# Jlink_OB.net
KiCad netlist of a schematic drawn in Altium Designer
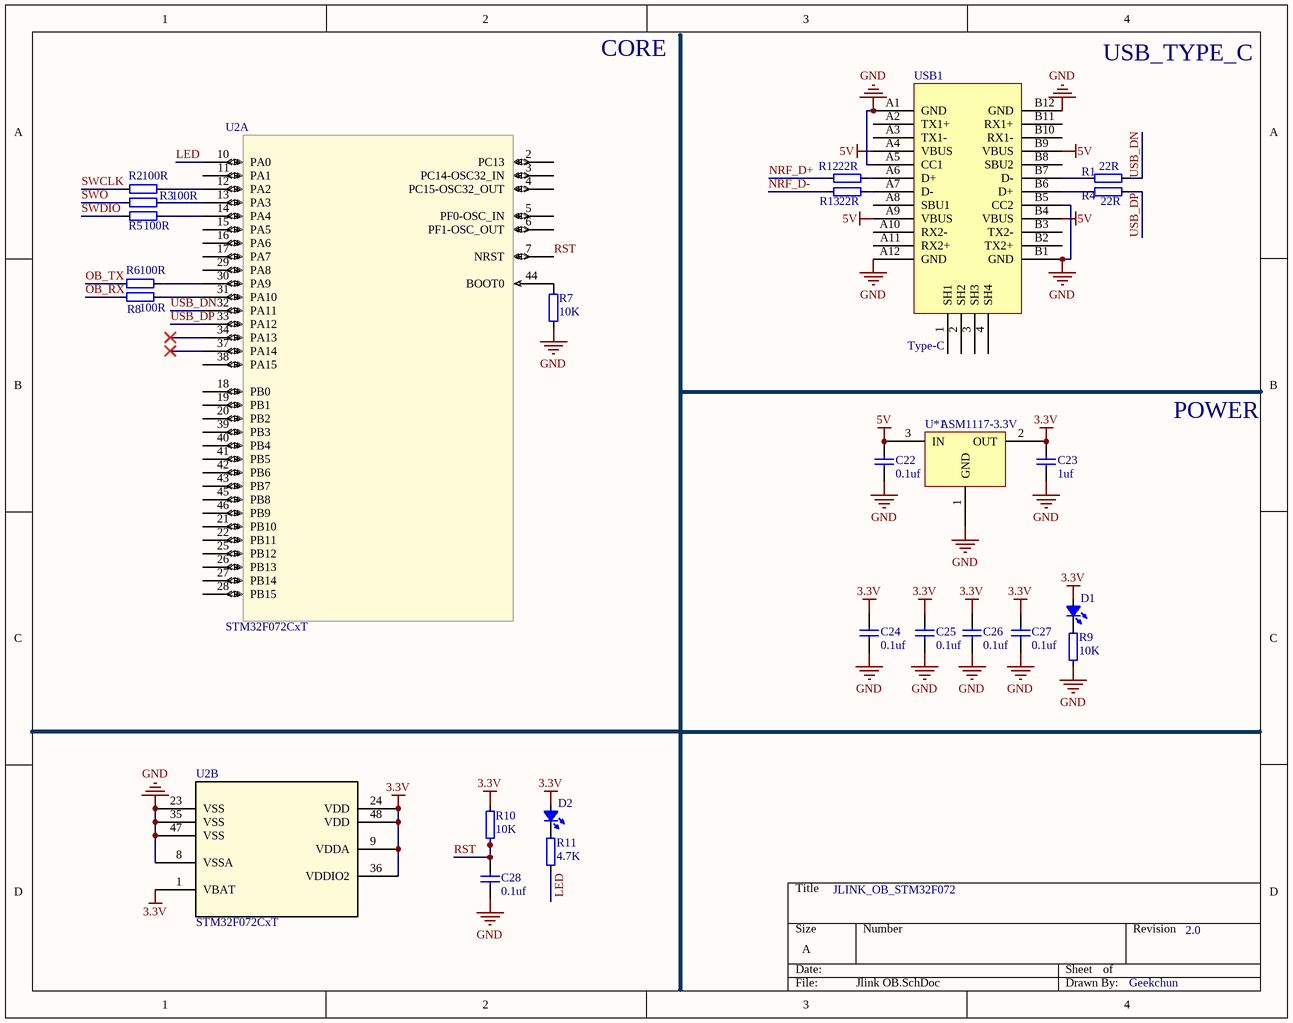
[diagram p0: Jlink OB.SchDoc]

(export (version "E")
  (design (tool "Eeschema 10.0.6"))
  (components
    (comp (ref "C22")
      (value "0.1uf")
      (footprint "C 0603_L")
      (description "Capacitor, NP0, ?.1pF")
      (fields (field (name "PART NUMBER") "C0402-1.2p") (field (name "PUBLISHER") "Nordic Semiconductor"))
      (libsource (lib "52") (part "CAP"))
    )
    (comp (ref "C23")
      (value "1uf")
      (footprint "C 0603_L")
      (description "Capacitor, NP0, ?.1pF")
      (fields (field (name "PART NUMBER") "C0402-1.2p") (field (name "PUBLISHER") "Nordic Semiconductor"))
      (libsource (lib "52") (part "CAP"))
    )
    (comp (ref "C24")
      (value "0.1uf")
      (footprint "C 0603_L")
      (description "Capacitor, NP0, ?.1pF")
      (fields (field (name "PART NUMBER") "C0402-1.2p") (field (name "PUBLISHER") "Nordic Semiconductor"))
      (libsource (lib "52") (part "CAP"))
    )
    (comp (ref "C25")
      (value "0.1uf")
      (footprint "C 0603_L")
      (description "Capacitor, NP0, ?.1pF")
      (fields (field (name "PART NUMBER") "C0402-1.2p") (field (name "PUBLISHER") "Nordic Semiconductor"))
      (libsource (lib "52") (part "CAP"))
    )
    (comp (ref "C26")
      (value "0.1uf")
      (footprint "C 0603_L")
      (description "Capacitor, NP0, ?.1pF")
      (fields (field (name "PART NUMBER") "C0402-1.2p") (field (name "PUBLISHER") "Nordic Semiconductor"))
      (libsource (lib "52") (part "CAP"))
    )
    (comp (ref "C27")
      (value "0.1uf")
      (footprint "C 0603_L")
      (description "Capacitor, NP0, ?.1pF")
      (fields (field (name "PART NUMBER") "C0402-1.2p") (field (name "PUBLISHER") "Nordic Semiconductor"))
      (libsource (lib "52") (part "CAP"))
    )
    (comp (ref "C28")
      (value "0.1uf")
      (footprint "C 0603_L")
      (description "Capacitor, NP0, ?.1pF")
      (fields (field (name "PART NUMBER") "C0402-1.2p") (field (name "PUBLISHER") "Nordic Semiconductor"))
      (libsource (lib "52") (part "CAP"))
    )
    (comp (ref "D1")
      (value "LED_0603")
      (footprint "LED 0603B")
      (description "LED")
      (libsource (lib "SCH_Active") (part "LED_0603"))
    )
    (comp (ref "D2")
      (value "LED_0603")
      (footprint "LED 0603B")
      (description "LED")
      (libsource (lib "SCH_Active") (part "LED_0603"))
    )
    (comp (ref "R1") (value "22R") (footprint "R 0603_L") (libsource (lib "电阻") (part "RES")))
    (comp (ref "R2") (value "100R") (footprint "R 0603_L") (libsource (lib "电阻") (part "RES")))
    (comp (ref "R3") (value "100R") (footprint "R 0603_L") (libsource (lib "电阻") (part "RES")))
    (comp (ref "R4") (value "22R") (footprint "R 0603_L") (libsource (lib "电阻") (part "RES")))
    (comp (ref "R5") (value "100R") (footprint "R 0603_L") (libsource (lib "电阻") (part "RES")))
    (comp (ref "R6") (value "100R") (footprint "R 0603_L") (libsource (lib "电阻") (part "RES")))
    (comp (ref "R7") (value "10K") (footprint "R 0603_L") (libsource (lib "电阻") (part "RES")))
    (comp (ref "R8") (value "100R") (footprint "R 0603_L") (libsource (lib "电阻") (part "RES")))
    (comp (ref "R9") (value "10K") (footprint "R 0603_L") (libsource (lib "电阻") (part "RES")))
    (comp (ref "R10") (value "10K") (footprint "R 0603_L") (libsource (lib "电阻") (part "RES")))
    (comp (ref "R11") (value "4.7K") (footprint "R 0603_L") (libsource (lib "电阻") (part "RES")))
    (comp (ref "R12") (value "22R") (footprint "R 0603_L") (libsource (lib "电阻") (part "RES")))
    (comp (ref "R13") (value "22R") (footprint "R 0603_L") (libsource (lib "电阻") (part "RES")))
    (comp (ref "U*1")
      (value "ASM1117-3.3V")
      (footprint "SOT-89")
      (description "三端可调或固定电压3.3V")
      (libsource (lib "STM32F103C及ASM1117") (part "ASM1117-3.3V"))
    )
    (comp (ref "U2")
      (value "STM32F072CxT")
      (footprint "LQFP48 7X7_L")
      (description "Imported")
      (fields
        (field (name "MANUFACTURER_PART_NUMBER") "stm32f072cxt")
        (field (name "COPYRIGHT") "Copyright (C) 2016 Accelerated Designs. All rights reserved")
      )
      (libsource (lib "STM32F072CB") (part "STM32F072CxT"))
    )
    (comp (ref "USB1") (value "Type-C") (footprint "usb typec") (libsource (lib "元件") (part "Type-C")))
  )
  (nets
    (net (code "1") (name "/LED") (class "Default")
      (node (ref "R11") (pin "1") (pinfunction "1_1") (pintype "passive"))
      (node (ref "U2") (pin "10") (pinfunction "PA0_10") (pintype "bidirectional"))
    )
    (net (code "2") (name "/NRF_D+") (class "Default")
      (node (ref "R12") (pin "1") (pinfunction "1_1") (pintype "passive"))
    )
    (net (code "3") (name "/NRF_D-") (class "Default")
      (node (ref "R13") (pin "1") (pinfunction "1_1") (pintype "passive"))
    )
    (net (code "4") (name "/OB_RX") (class "Default")
      (node (ref "R8") (pin "1") (pinfunction "1_1") (pintype "passive"))
    )
    (net (code "5") (name "/OB_TX") (class "Default")
      (node (ref "R6") (pin "1") (pinfunction "1_1") (pintype "passive"))
    )
    (net (code "6") (name "/RST") (class "Default")
      (node (ref "C28") (pin "2") (pinfunction "2_2") (pintype "passive"))
      (node (ref "R10") (pin "1") (pinfunction "1_1") (pintype "passive"))
      (node (ref "U2") (pin "7") (pinfunction "NRST_7") (pintype "bidirectional"))
    )
    (net (code "7") (name "/SWCLK") (class "Default")
      (node (ref "R2") (pin "1") (pinfunction "1_1") (pintype "passive"))
    )
    (net (code "8") (name "/SWDIO") (class "Default")
      (node (ref "R5") (pin "1") (pinfunction "1_1") (pintype "passive"))
    )
    (net (code "9") (name "/SWO") (class "Default")
      (node (ref "R3") (pin "1") (pinfunction "1_1") (pintype "passive"))
    )
    (net (code "10") (name "/USB_DN") (class "Default")
      (node (ref "R1") (pin "2") (pinfunction "2_2") (pintype "passive"))
      (node (ref "U2") (pin "32") (pinfunction "PA11_32") (pintype "bidirectional"))
    )
    (net (code "11") (name "/USB_DP") (class "Default")
      (node (ref "R4") (pin "2") (pinfunction "2_2") (pintype "passive"))
      (node (ref "U2") (pin "33") (pinfunction "PA12_33") (pintype "bidirectional"))
    )
    (net (code "12") (name "3.3V") (class "Default")
      (node (ref "C23") (pin "2") (pinfunction "2_2") (pintype "passive"))
      (node (ref "C24") (pin "2") (pinfunction "2_2") (pintype "passive"))
      (node (ref "C25") (pin "2") (pinfunction "2_2") (pintype "passive"))
      (node (ref "C26") (pin "2") (pinfunction "2_2") (pintype "passive"))
      (node (ref "C27") (pin "2") (pinfunction "2_2") (pintype "passive"))
      (node (ref "D1") (pin "1") (pinfunction "A_1") (pintype "passive"))
      (node (ref "D2") (pin "1") (pinfunction "A_1") (pintype "passive"))
      (node (ref "R10") (pin "2") (pinfunction "2_2") (pintype "passive"))
      (node (ref "U*1") (pin "2") (pinfunction "OUT_2") (pintype "passive"))
      (node (ref "U2") (pin "1") (pinfunction "VBAT_1") (pintype "power_in"))
      (node (ref "U2") (pin "24") (pinfunction "VDD_24") (pintype "power_in"))
      (node (ref "U2") (pin "36") (pinfunction "VDDIO2_36") (pintype "power_in"))
      (node (ref "U2") (pin "48") (pinfunction "VDD_48") (pintype "power_in"))
      (node (ref "U2") (pin "9") (pinfunction "VDDA_9") (pintype "power_in"))
    )
    (net (code "13") (name "5V") (class "Default")
      (node (ref "C22") (pin "2") (pinfunction "2_2") (pintype "passive"))
      (node (ref "U*1") (pin "3") (pinfunction "IN_3") (pintype "passive"))
      (node (ref "USB1") (pin "A4") (pinfunction "VBUS_A4") (pintype "passive"))
      (node (ref "USB1") (pin "A9") (pinfunction "VBUS_A9") (pintype "passive"))
      (node (ref "USB1") (pin "B4") (pinfunction "VBUS_B4") (pintype "passive"))
      (node (ref "USB1") (pin "B9") (pinfunction "VBUS_B9") (pintype "passive"))
    )
    (net (code "14") (name "GND") (class "Default")
      (node (ref "C22") (pin "1") (pinfunction "1_1") (pintype "passive"))
      (node (ref "C23") (pin "1") (pinfunction "1_1") (pintype "passive"))
      (node (ref "C24") (pin "1") (pinfunction "1_1") (pintype "passive"))
      (node (ref "C25") (pin "1") (pinfunction "1_1") (pintype "passive"))
      (node (ref "C26") (pin "1") (pinfunction "1_1") (pintype "passive"))
      (node (ref "C27") (pin "1") (pinfunction "1_1") (pintype "passive"))
      (node (ref "C28") (pin "1") (pinfunction "1_1") (pintype "passive"))
      (node (ref "R7") (pin "2") (pinfunction "2_2") (pintype "passive"))
      (node (ref "R9") (pin "1") (pinfunction "1_1") (pintype "passive"))
      (node (ref "U*1") (pin "1") (pinfunction "GND_1") (pintype "passive"))
      (node (ref "U2") (pin "23") (pinfunction "VSS_23") (pintype "power_in"))
      (node (ref "U2") (pin "35") (pinfunction "VSS_35") (pintype "power_in"))
      (node (ref "U2") (pin "47") (pinfunction "VSS_47") (pintype "power_in"))
      (node (ref "U2") (pin "8") (pinfunction "VSSA_8") (pintype "power_in"))
      (node (ref "USB1") (pin "A1") (pinfunction "GND_A1") (pintype "passive"))
      (node (ref "USB1") (pin "A12") (pinfunction "GND_A12") (pintype "passive"))
      (node (ref "USB1") (pin "A5") (pinfunction "CC1_A5") (pintype "passive"))
      (node (ref "USB1") (pin "B1") (pinfunction "GND_B1") (pintype "passive"))
      (node (ref "USB1") (pin "B12") (pinfunction "GND_B12") (pintype "passive"))
      (node (ref "USB1") (pin "B5") (pinfunction "CC2_B5") (pintype "passive"))
    )
    (net (code "15") (name "Net-(D1-K)") (class "Default")
      (node (ref "D1") (pin "2") (pinfunction "K_2") (pintype "passive"))
      (node (ref "R9") (pin "2") (pinfunction "2_2") (pintype "passive"))
    )
    (net (code "16") (name "Net-(D2-K)") (class "Default")
      (node (ref "D2") (pin "2") (pinfunction "K_2") (pintype "passive"))
      (node (ref "R11") (pin "2") (pinfunction "2_2") (pintype "passive"))
    )
    (net (code "17") (name "Net-(R1-Pad1)") (class "Default")
      (node (ref "R1") (pin "1") (pinfunction "1_1") (pintype "passive"))
      (node (ref "USB1") (pin "B7") (pinfunction "D-_B7") (pintype "passive"))
    )
    (net (code "18") (name "Net-(R4-Pad1)") (class "Default")
      (node (ref "R4") (pin "1") (pinfunction "1_1") (pintype "passive"))
      (node (ref "USB1") (pin "B6") (pinfunction "D+_B6") (pintype "passive"))
    )
    (net (code "19") (name "Net-(R12-Pad2)") (class "Default")
      (node (ref "R12") (pin "2") (pinfunction "2_2") (pintype "passive"))
      (node (ref "USB1") (pin "A6") (pinfunction "D+_A6") (pintype "passive"))
    )
    (net (code "20") (name "Net-(R13-Pad2)") (class "Default")
      (node (ref "R13") (pin "2") (pinfunction "2_2") (pintype "passive"))
      (node (ref "USB1") (pin "A7") (pinfunction "D-_A7") (pintype "passive"))
    )
    (net (code "21") (name "Net-(U2A-BOOT0)") (class "Default")
      (node (ref "R7") (pin "1") (pinfunction "1_1") (pintype "passive"))
      (node (ref "U2") (pin "44") (pinfunction "BOOT0_44") (pintype "input"))
    )
    (net (code "22") (name "Net-(U2A-PA2)") (class "Default")
      (node (ref "R2") (pin "2") (pinfunction "2_2") (pintype "passive"))
      (node (ref "U2") (pin "12") (pinfunction "PA2_12") (pintype "bidirectional"))
    )
    (net (code "23") (name "Net-(U2A-PA3)") (class "Default")
      (node (ref "R3") (pin "2") (pinfunction "2_2") (pintype "passive"))
      (node (ref "U2") (pin "13") (pinfunction "PA3_13") (pintype "bidirectional"))
    )
    (net (code "24") (name "Net-(U2A-PA4)") (class "Default")
      (node (ref "R5") (pin "2") (pinfunction "2_2") (pintype "passive"))
      (node (ref "U2") (pin "14") (pinfunction "PA4_14") (pintype "bidirectional"))
    )
    (net (code "25") (name "Net-(U2A-PA9)") (class "Default")
      (node (ref "R6") (pin "2") (pinfunction "2_2") (pintype "passive"))
      (node (ref "U2") (pin "30") (pinfunction "PA9_30") (pintype "bidirectional"))
    )
    (net (code "26") (name "Net-(U2A-PA10)") (class "Default")
      (node (ref "R8") (pin "2") (pinfunction "2_2") (pintype "passive"))
      (node (ref "U2") (pin "31") (pinfunction "PA10_31") (pintype "bidirectional"))
    )
    (net (code "27") (name "unconnected-(U2A-PA1-Pad11)") (class "Default")
      (node (ref "U2") (pin "11") (pinfunction "PA1_11") (pintype "bidirectional"))
    )
    (net (code "28") (name "unconnected-(U2A-PA5-Pad15)") (class "Default")
      (node (ref "U2") (pin "15") (pinfunction "PA5_15") (pintype "bidirectional"))
    )
    (net (code "29") (name "unconnected-(U2A-PA6-Pad16)") (class "Default")
      (node (ref "U2") (pin "16") (pinfunction "PA6_16") (pintype "bidirectional"))
    )
    (net (code "30") (name "unconnected-(U2A-PA7-Pad17)") (class "Default")
      (node (ref "U2") (pin "17") (pinfunction "PA7_17") (pintype "bidirectional"))
    )
    (net (code "31") (name "unconnected-(U2A-PA8-Pad29)") (class "Default")
      (node (ref "U2") (pin "29") (pinfunction "PA8_29") (pintype "bidirectional"))
    )
    (net (code "32") (name "unconnected-(U2A-PA13-Pad34)") (class "Default")
      (node (ref "U2") (pin "34") (pinfunction "PA13_34") (pintype "bidirectional+no_connect"))
    )
    (net (code "33") (name "unconnected-(U2A-PA14-Pad37)") (class "Default")
      (node (ref "U2") (pin "37") (pinfunction "PA14_37") (pintype "bidirectional+no_connect"))
    )
    (net (code "34") (name "unconnected-(U2A-PA15-Pad38)") (class "Default")
      (node (ref "U2") (pin "38") (pinfunction "PA15_38") (pintype "bidirectional"))
    )
    (net (code "35") (name "unconnected-(U2A-PB0-Pad18)") (class "Default")
      (node (ref "U2") (pin "18") (pinfunction "PB0_18") (pintype "bidirectional"))
    )
    (net (code "36") (name "unconnected-(U2A-PB1-Pad19)") (class "Default")
      (node (ref "U2") (pin "19") (pinfunction "PB1_19") (pintype "bidirectional"))
    )
    (net (code "37") (name "unconnected-(U2A-PB2-Pad20)") (class "Default")
      (node (ref "U2") (pin "20") (pinfunction "PB2_20") (pintype "bidirectional"))
    )
    (net (code "38") (name "unconnected-(U2A-PB3-Pad39)") (class "Default")
      (node (ref "U2") (pin "39") (pinfunction "PB3_39") (pintype "bidirectional"))
    )
    (net (code "39") (name "unconnected-(U2A-PB4-Pad40)") (class "Default")
      (node (ref "U2") (pin "40") (pinfunction "PB4_40") (pintype "bidirectional"))
    )
    (net (code "40") (name "unconnected-(U2A-PB5-Pad41)") (class "Default")
      (node (ref "U2") (pin "41") (pinfunction "PB5_41") (pintype "bidirectional"))
    )
    (net (code "41") (name "unconnected-(U2A-PB6-Pad42)") (class "Default")
      (node (ref "U2") (pin "42") (pinfunction "PB6_42") (pintype "bidirectional"))
    )
    (net (code "42") (name "unconnected-(U2A-PB7-Pad43)") (class "Default")
      (node (ref "U2") (pin "43") (pinfunction "PB7_43") (pintype "bidirectional"))
    )
    (net (code "43") (name "unconnected-(U2A-PB8-Pad45)") (class "Default")
      (node (ref "U2") (pin "45") (pinfunction "PB8_45") (pintype "bidirectional"))
    )
    (net (code "44") (name "unconnected-(U2A-PB9-Pad46)") (class "Default")
      (node (ref "U2") (pin "46") (pinfunction "PB9_46") (pintype "bidirectional"))
    )
    (net (code "45") (name "unconnected-(U2A-PB10-Pad21)") (class "Default")
      (node (ref "U2") (pin "21") (pinfunction "PB10_21") (pintype "bidirectional"))
    )
    (net (code "46") (name "unconnected-(U2A-PB11-Pad22)") (class "Default")
      (node (ref "U2") (pin "22") (pinfunction "PB11_22") (pintype "bidirectional"))
    )
    (net (code "47") (name "unconnected-(U2A-PB12-Pad25)") (class "Default")
      (node (ref "U2") (pin "25") (pinfunction "PB12_25") (pintype "bidirectional"))
    )
    (net (code "48") (name "unconnected-(U2A-PB13-Pad26)") (class "Default")
      (node (ref "U2") (pin "26") (pinfunction "PB13_26") (pintype "bidirectional"))
    )
    (net (code "49") (name "unconnected-(U2A-PB14-Pad27)") (class "Default")
      (node (ref "U2") (pin "27") (pinfunction "PB14_27") (pintype "bidirectional"))
    )
    (net (code "50") (name "unconnected-(U2A-PB15-Pad28)") (class "Default")
      (node (ref "U2") (pin "28") (pinfunction "PB15_28") (pintype "bidirectional"))
    )
    (net (code "51") (name "unconnected-(U2A-PC13-Pad2)") (class "Default")
      (node (ref "U2") (pin "2") (pinfunction "PC13_2") (pintype "bidirectional"))
    )
    (net (code "52") (name "unconnected-(U2A-PC14-OSC32_IN-Pad3)") (class "Default")
      (node (ref "U2") (pin "3") (pinfunction "PC14-OSC32_IN_3") (pintype "bidirectional"))
    )
    (net (code "53") (name "unconnected-(U2A-PC15-OSC32_OUT-Pad4)") (class "Default")
      (node (ref "U2") (pin "4") (pinfunction "PC15-OSC32_OUT_4") (pintype "bidirectional"))
    )
    (net (code "54") (name "unconnected-(U2A-PF0-OSC_IN-Pad5)") (class "Default")
      (node (ref "U2") (pin "5") (pinfunction "PF0-OSC_IN_5") (pintype "bidirectional"))
    )
    (net (code "55") (name "unconnected-(U2A-PF1-OSC_OUT-Pad6)") (class "Default")
      (node (ref "U2") (pin "6") (pinfunction "PF1-OSC_OUT_6") (pintype "bidirectional"))
    )
    (net (code "56") (name "unconnected-(USB1-RX1+-PadB11)") (class "Default")
      (node (ref "USB1") (pin "B11") (pinfunction "RX1+_B11") (pintype "passive"))
    )
    (net (code "57") (name "unconnected-(USB1-RX1--PadB10)") (class "Default")
      (node (ref "USB1") (pin "B10") (pinfunction "RX1-_B10") (pintype "passive"))
    )
    (net (code "58") (name "unconnected-(USB1-RX2+-PadA11)") (class "Default")
      (node (ref "USB1") (pin "A11") (pinfunction "RX2+_A11") (pintype "passive"))
    )
    (net (code "59") (name "unconnected-(USB1-RX2--PadA10)") (class "Default")
      (node (ref "USB1") (pin "A10") (pinfunction "RX2-_A10") (pintype "passive"))
    )
    (net (code "60") (name "unconnected-(USB1-SBU1-PadA8)") (class "Default")
      (node (ref "USB1") (pin "A8") (pinfunction "SBU1_A8") (pintype "passive"))
    )
    (net (code "61") (name "unconnected-(USB1-SBU2-PadB8)") (class "Default")
      (node (ref "USB1") (pin "B8") (pinfunction "SBU2_B8") (pintype "passive"))
    )
    (net (code "62") (name "unconnected-(USB1-SH1-Pad1)") (class "Default")
      (node (ref "USB1") (pin "1") (pinfunction "SH1_1") (pintype "passive"))
    )
    (net (code "63") (name "unconnected-(USB1-SH2-Pad2)") (class "Default")
      (node (ref "USB1") (pin "2") (pinfunction "SH2_2") (pintype "passive"))
    )
    (net (code "64") (name "unconnected-(USB1-SH3-Pad3)") (class "Default")
      (node (ref "USB1") (pin "3") (pinfunction "SH3_3") (pintype "passive"))
    )
    (net (code "65") (name "unconnected-(USB1-SH4-Pad4)") (class "Default")
      (node (ref "USB1") (pin "4") (pinfunction "SH4_4") (pintype "passive"))
    )
    (net (code "66") (name "unconnected-(USB1-TX1+-PadA2)") (class "Default")
      (node (ref "USB1") (pin "A2") (pinfunction "TX1+_A2") (pintype "passive"))
    )
    (net (code "67") (name "unconnected-(USB1-TX1--PadA3)") (class "Default")
      (node (ref "USB1") (pin "A3") (pinfunction "TX1-_A3") (pintype "passive"))
    )
    (net (code "68") (name "unconnected-(USB1-TX2+-PadB2)") (class "Default")
      (node (ref "USB1") (pin "B2") (pinfunction "TX2+_B2") (pintype "passive"))
    )
    (net (code "69") (name "unconnected-(USB1-TX2--PadB3)") (class "Default")
      (node (ref "USB1") (pin "B3") (pinfunction "TX2-_B3") (pintype "passive"))
    )
  )
)
